# wifi.net
KiCad netlist of a schematic drawn in Altium Designer
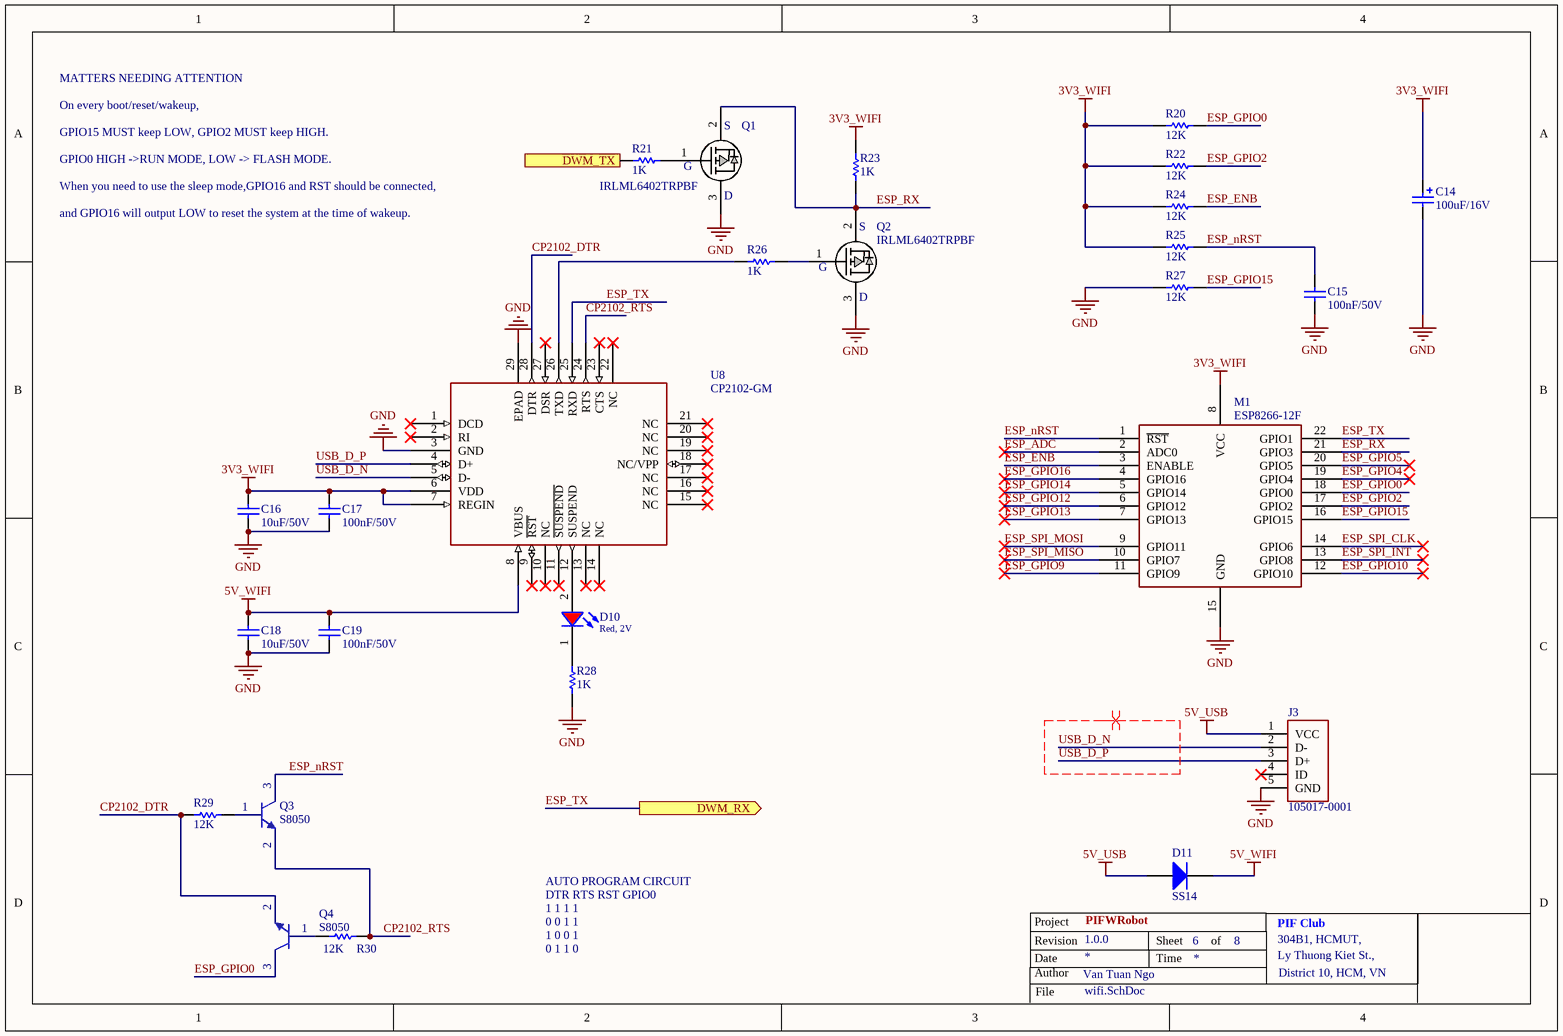
[diagram p0: wifi.SchDoc]

(export (version "E")
  (design (tool "Eeschema 10.0.6"))
  (components
    (comp (ref "C14")
      (value "100uF/16V")
      (footprint "CAP_SM_TAN")
      (fields
        (field (name "MANUFACTURER") "Nichicon")
        (field (name "MANUFACTURER PART NUMBER") "UWX1C101MCL1GB")
        (field (name "Comment") "TAJB107M006RNJ")
      )
      (libsource (lib "Capacitor") (part "Cap-Tan-100uF-16V"))
    )
    (comp (ref "C15")
      (value "100nF/50V")
      (footprint "CAP-SM-0805")
      (description "CAP CER 0.1UF 50V Y5V 0805")
      (fields
        (field (name "MANUFACTURER") "Samsung Electro-Mechanics")
        (field (name "MANUFACTURER PART NUMBER") "CL21F104ZBCNNNC")
      )
      (libsource (lib "Capacitor") (part "Cap-100nF-50V-0805"))
    )
    (comp (ref "C16")
      (value "10uF/50V")
      (footprint "CAP-SM-0805")
      (description "CAP CER 10UF 50V X5R 0805")
      (fields
        (field (name "MANUFACTURER") "Yageo")
        (field (name "MANUFACTURER PART NUMBER") "CC0805KKX5R9BB106")
      )
      (libsource (lib "capacitor-smd") (part "Cap-10uF-50V-0805"))
    )
    (comp (ref "C17")
      (value "100nF/50V")
      (footprint "CAP-SM-0805")
      (description "CAP CER 0.1UF 50V Y5V 0805")
      (fields
        (field (name "MANUFACTURER") "Samsung Electro-Mechanics")
        (field (name "MANUFACTURER PART NUMBER") "CL21F104ZBCNNNC")
      )
      (libsource (lib "capacitor-smd") (part "Cap-100nF-50V-0805"))
    )
    (comp (ref "C18")
      (value "10uF/50V")
      (footprint "CAP-SM-0805")
      (description "CAP CER 10UF 50V X5R 0805")
      (fields
        (field (name "MANUFACTURER") "Yageo")
        (field (name "MANUFACTURER PART NUMBER") "CC0805KKX5R9BB106")
      )
      (libsource (lib "capacitor-smd") (part "Cap-10uF-50V-0805"))
    )
    (comp (ref "C19")
      (value "100nF/50V")
      (footprint "CAP-SM-0805")
      (description "CAP CER 0.1UF 50V Y5V 0805")
      (fields
        (field (name "MANUFACTURER") "Samsung Electro-Mechanics")
        (field (name "MANUFACTURER PART NUMBER") "CL21F104ZBCNNNC")
      )
      (libsource (lib "capacitor-smd") (part "Cap-100nF-50V-0805"))
    )
    (comp (ref "D10")
      (value "Red, 2V")
      (footprint "WL-SMCW_0805")
      (description "WL-SMCW SMT Mono-color Chip LED Waterclear, size 0805, Red, 2V, 140deg")
      (fields
        (field (name "PART NUMBER") "150080RS75000")
        (field (name "LOCAL SUPPLIER PARTNUMBER") "x")
        (field (name "PUBLISHER") "Wurth Elektronik")
      )
      (libsource (lib "LED") (part "0805-Red"))
    )
    (comp (ref "D11")
      (value "SS14")
      (footprint "SS14")
      (description "DIODE SCHOTTKY 40V 1A SMA")
      (fields (field (name "MANUFACTURER") "ON Semiconductor"))
      (libsource (lib "Diode") (part "Diode-SS14"))
    )
    (comp (ref "J3")
      (value "105017-0001")
      (footprint "Micro-USB-Female")
      (description "CONN RCPT USB2.0 MICRO B SMD R/A")
      (fields
        (field (name "LOCAL SUPPLIER PART NUMBER") "x")
        (field (name "COPYRIGHT") "Copyright (C) 2018 Accelerated Designs. All rights reserved")
      )
      (libsource (lib "header-connector") (part "Micro-USB-Female"))
    )
    (comp (ref "M1")
      (value "ESP8266-12F")
      (footprint "ESP8266-12F")
      (fields (field (name "LOCAL SUPPLIER PART NUMBER") "x"))
      (libsource (lib "PIFWRobot") (part "ESP8266-12F"))
    )
    (comp (ref "Q1")
      (value "IRLML6402TRPBF")
      (footprint "SOT23_NEX")
      (description "P-Channel 20V 3.7A (Ta) 1.3W (Ta) Surface Mount Micro3™/SOT-23")
      (libsource (lib "MOSFET") (part "IRLML6402TRPBF"))
    )
    (comp (ref "Q2")
      (value "IRLML6402TRPBF")
      (footprint "SOT23_NEX")
      (description "P-Channel 20V 3.7A (Ta) 1.3W (Ta) Surface Mount Micro3™/SOT-23")
      (libsource (lib "MOSFET") (part "IRLML6402TRPBF"))
    )
    (comp (ref "Q3") (value "S8050") (footprint "SOT23_NEX") (libsource (lib "BJT") (part "S8050")))
    (comp (ref "Q4") (value "S8050") (footprint "SOT23_NEX") (libsource (lib "BJT") (part "S8050")))
    (comp (ref "R20")
      (value "12K")
      (footprint "resistor-smd:RES-SM-0805")
      (description "RES 12 KOHM JUMPER 0805")
      (fields
        (field (name "MANUFACTURER") "Vishay Thin Film")
        (field (name "MANUFACTURER PART NUMBER") "PAT0805E3121BST1")
      )
      (libsource (lib "resistor-smd") (part "Res-12K-0805"))
    )
    (comp (ref "R21")
      (value "1K")
      (footprint "resistor-smd:RES-SM-0805")
      (description "RES 1K OHM 1% 1/4W 0805")
      (fields
        (field (name "MANUFACTURER") "Stackpole Electronics Inc")
        (field (name "MANUFACTURER PART NUMBER") "RNCP0805FTD1K00")
      )
      (libsource (lib "resistor-smd") (part "Res-1K-0805"))
    )
    (comp (ref "R22")
      (value "12K")
      (footprint "resistor-smd:RES-SM-0805")
      (description "RES 12 KOHM JUMPER 0805")
      (fields
        (field (name "MANUFACTURER") "Vishay Thin Film")
        (field (name "MANUFACTURER PART NUMBER") "PAT0805E3121BST1")
      )
      (libsource (lib "resistor-smd") (part "Res-12K-0805"))
    )
    (comp (ref "R23")
      (value "1K")
      (footprint "resistor-smd:RES-SM-0805")
      (description "RES 1K OHM 1% 1/4W 0805")
      (fields
        (field (name "MANUFACTURER") "Stackpole Electronics Inc")
        (field (name "MANUFACTURER PART NUMBER") "RNCP0805FTD1K00")
      )
      (libsource (lib "resistor-smd") (part "Res-1K-0805"))
    )
    (comp (ref "R24")
      (value "12K")
      (footprint "resistor-smd:RES-SM-0805")
      (description "RES 12 KOHM JUMPER 0805")
      (fields
        (field (name "MANUFACTURER") "Vishay Thin Film")
        (field (name "MANUFACTURER PART NUMBER") "PAT0805E3121BST1")
      )
      (libsource (lib "resistor-smd") (part "Res-12K-0805"))
    )
    (comp (ref "R25")
      (value "12K")
      (footprint "resistor-smd:RES-SM-0805")
      (description "RES 12 KOHM JUMPER 0805")
      (fields
        (field (name "MANUFACTURER") "Vishay Thin Film")
        (field (name "MANUFACTURER PART NUMBER") "PAT0805E3121BST1")
      )
      (libsource (lib "resistor-smd") (part "Res-12K-0805"))
    )
    (comp (ref "R26")
      (value "1K")
      (footprint "resistor-smd:RES-SM-0805")
      (description "RES 1K OHM 1% 1/4W 0805")
      (fields
        (field (name "MANUFACTURER") "Stackpole Electronics Inc")
        (field (name "MANUFACTURER PART NUMBER") "RNCP0805FTD1K00")
      )
      (libsource (lib "resistor-smd") (part "Res-1K-0805"))
    )
    (comp (ref "R27")
      (value "12K")
      (footprint "resistor-smd:RES-SM-0805")
      (description "RES 12 KOHM JUMPER 0805")
      (fields
        (field (name "MANUFACTURER") "Vishay Thin Film")
        (field (name "MANUFACTURER PART NUMBER") "PAT0805E3121BST1")
      )
      (libsource (lib "resistor-smd") (part "Res-12K-0805"))
    )
    (comp (ref "R28")
      (value "1K")
      (footprint "resistor-smd:RES-SM-0805")
      (description "RES 1K OHM 1% 1/4W 0805")
      (fields
        (field (name "MANUFACTURER") "Stackpole Electronics Inc")
        (field (name "MANUFACTURER PART NUMBER") "RNCP0805FTD1K00")
      )
      (libsource (lib "resistor-smd") (part "Res-1K-0805"))
    )
    (comp (ref "R29")
      (value "12K")
      (footprint "resistor-smd:RES-SM-0805")
      (description "RES 12 KOHM JUMPER 0805")
      (fields
        (field (name "MANUFACTURER") "Vishay Thin Film")
        (field (name "MANUFACTURER PART NUMBER") "PAT0805E3121BST1")
      )
      (libsource (lib "resistor-smd") (part "Res-12K-0805"))
    )
    (comp (ref "R30")
      (value "12K")
      (footprint "resistor-smd:RES-SM-0805")
      (description "RES 12 KOHM JUMPER 0805")
      (fields
        (field (name "MANUFACTURER") "Vishay Thin Film")
        (field (name "MANUFACTURER PART NUMBER") "PAT0805E3121BST1")
      )
      (libsource (lib "resistor-smd") (part "Res-12K-0805"))
    )
    (comp (ref "U8")
      (value "CP2102-GM")
      (footprint "QFN28_5X5_SIL")
      (fields (field (name "COPYRIGHT") "Copyright (C) 2018 Accelerated Designs. All rights reserved"))
      (libsource (lib "PIFWRobot") (part "CP2102-GM"))
    )
  )
  (nets
    (net (code "1") (name "/CP2102_DTR") (class "Default")
      (node (ref "Q4") (pin "2") (pinfunction "E_2") (pintype "passive"))
      (node (ref "R29") (pin "1") (pinfunction "1_1") (pintype "passive"))
      (node (ref "U8") (pin "28") (pinfunction "DTR_28") (pintype "output"))
    )
    (net (code "2") (name "/CP2102_RTS") (class "Default")
      (node (ref "Q3") (pin "2") (pinfunction "E_2") (pintype "passive"))
      (node (ref "R30") (pin "2") (pinfunction "2_2") (pintype "passive"))
      (node (ref "U8") (pin "24") (pinfunction "RTS_24") (pintype "output"))
    )
    (net (code "3") (name "/DWM_TX") (class "Default")
      (node (ref "R21") (pin "1") (pinfunction "1_1") (pintype "passive"))
    )
    (net (code "4") (name "/ESP_ADC") (class "Default")
      (node (ref "M1") (pin "2") (pinfunction "ADC0_2") (pintype "passive+no_connect"))
    )
    (net (code "5") (name "/ESP_ENB") (class "Default")
      (node (ref "M1") (pin "3") (pinfunction "ENABLE_3") (pintype "passive"))
      (node (ref "R24") (pin "2") (pinfunction "2_2") (pintype "passive"))
    )
    (net (code "6") (name "/ESP_GPIO0") (class "Default")
      (node (ref "M1") (pin "18") (pinfunction "GPIO0_18") (pintype "passive"))
      (node (ref "Q4") (pin "3") (pinfunction "C_3") (pintype "passive"))
      (node (ref "R20") (pin "2") (pinfunction "2_2") (pintype "passive"))
    )
    (net (code "7") (name "/ESP_GPIO2") (class "Default")
      (node (ref "M1") (pin "17") (pinfunction "GPIO2_17") (pintype "passive"))
      (node (ref "R22") (pin "2") (pinfunction "2_2") (pintype "passive"))
    )
    (net (code "8") (name "/ESP_GPIO4") (class "Default")
      (node (ref "M1") (pin "19") (pinfunction "GPIO4_19") (pintype "passive+no_connect"))
    )
    (net (code "9") (name "/ESP_GPIO5") (class "Default")
      (node (ref "M1") (pin "20") (pinfunction "GPIO5_20") (pintype "passive+no_connect"))
    )
    (net (code "10") (name "/ESP_GPIO9") (class "Default")
      (node (ref "M1") (pin "11") (pinfunction "GPIO9_11") (pintype "passive+no_connect"))
    )
    (net (code "11") (name "/ESP_GPIO10") (class "Default")
      (node (ref "M1") (pin "12") (pinfunction "GPIO10_12") (pintype "passive+no_connect"))
    )
    (net (code "12") (name "/ESP_GPIO12") (class "Default")
      (node (ref "M1") (pin "6") (pinfunction "GPIO12_6") (pintype "passive+no_connect"))
    )
    (net (code "13") (name "/ESP_GPIO13") (class "Default")
      (node (ref "M1") (pin "7") (pinfunction "GPIO13_7") (pintype "passive+no_connect"))
    )
    (net (code "14") (name "/ESP_GPIO14") (class "Default")
      (node (ref "M1") (pin "5") (pinfunction "GPIO14_5") (pintype "passive+no_connect"))
    )
    (net (code "15") (name "/ESP_GPIO15") (class "Default")
      (node (ref "M1") (pin "16") (pinfunction "GPIO15_16") (pintype "passive"))
      (node (ref "R27") (pin "2") (pinfunction "2_2") (pintype "passive"))
    )
    (net (code "16") (name "/ESP_GPIO16") (class "Default")
      (node (ref "M1") (pin "4") (pinfunction "GPIO16_4") (pintype "passive+no_connect"))
    )
    (net (code "17") (name "/ESP_RX") (class "Default")
      (node (ref "M1") (pin "21") (pinfunction "GPIO3_21") (pintype "passive"))
      (node (ref "Q1") (pin "2") (pinfunction "S_2") (pintype "passive"))
      (node (ref "Q2") (pin "2") (pinfunction "S_2") (pintype "passive"))
      (node (ref "R23") (pin "1") (pinfunction "1_1") (pintype "passive"))
    )
    (net (code "18") (name "/ESP_SPI_CLK") (class "Default")
      (node (ref "M1") (pin "14") (pinfunction "GPIO6_14") (pintype "passive+no_connect"))
    )
    (net (code "19") (name "/ESP_SPI_INT") (class "Default")
      (node (ref "M1") (pin "13") (pinfunction "GPIO8_13") (pintype "passive+no_connect"))
    )
    (net (code "20") (name "/ESP_SPI_MISO") (class "Default")
      (node (ref "M1") (pin "10") (pinfunction "GPIO7_10") (pintype "passive+no_connect"))
    )
    (net (code "21") (name "/ESP_SPI_MOSI") (class "Default")
      (node (ref "M1") (pin "9") (pinfunction "GPIO11_9") (pintype "passive+no_connect"))
    )
    (net (code "22") (name "/ESP_TX") (class "Default")
      (node (ref "M1") (pin "22") (pinfunction "GPIO1_22") (pintype "passive"))
      (node (ref "U8") (pin "25") (pinfunction "RXD_25") (pintype "input"))
    )
    (net (code "23") (name "/ESP_nRST") (class "Default")
      (node (ref "C15") (pin "2") (pinfunction "2_2") (pintype "passive"))
      (node (ref "M1") (pin "1") (pinfunction "~{RST}_1") (pintype "passive"))
      (node (ref "Q3") (pin "3") (pinfunction "C_3") (pintype "passive"))
      (node (ref "R25") (pin "2") (pinfunction "2_2") (pintype "passive"))
    )
    (net (code "24") (name "/USB_D_N") (class "Default")
      (node (ref "J3") (pin "2") (pinfunction "D-_2") (pintype "passive"))
      (node (ref "U8") (pin "5") (pinfunction "D-_5") (pintype "bidirectional"))
    )
    (net (code "25") (name "/USB_D_P") (class "Default")
      (node (ref "J3") (pin "3") (pinfunction "D+_3") (pintype "passive"))
      (node (ref "U8") (pin "4") (pinfunction "D+_4") (pintype "bidirectional"))
    )
    (net (code "26") (name "3V3_WIFI") (class "Default")
      (node (ref "C14") (pin "1") (pinfunction "1_1") (pintype "passive"))
      (node (ref "C16") (pin "2") (pinfunction "2_2") (pintype "passive"))
      (node (ref "C17") (pin "2") (pinfunction "2_2") (pintype "passive"))
      (node (ref "M1") (pin "8") (pinfunction "VCC_8") (pintype "passive"))
      (node (ref "R20") (pin "1") (pinfunction "1_1") (pintype "passive"))
      (node (ref "R22") (pin "1") (pinfunction "1_1") (pintype "passive"))
      (node (ref "R23") (pin "2") (pinfunction "2_2") (pintype "passive"))
      (node (ref "R24") (pin "1") (pinfunction "1_1") (pintype "passive"))
      (node (ref "R25") (pin "1") (pinfunction "1_1") (pintype "passive"))
      (node (ref "U8") (pin "6") (pinfunction "VDD_6") (pintype "power_in"))
      (node (ref "U8") (pin "7") (pinfunction "REGIN_7") (pintype "input"))
    )
    (net (code "27") (name "5V_USB") (class "Default")
      (node (ref "D11") (pin "2") (pinfunction "A_2") (pintype "passive"))
      (node (ref "J3") (pin "1") (pinfunction "VCC_1") (pintype "power_in"))
    )
    (net (code "28") (name "5V_WIFI") (class "Default")
      (node (ref "C18") (pin "2") (pinfunction "2_2") (pintype "passive"))
      (node (ref "C19") (pin "2") (pinfunction "2_2") (pintype "passive"))
      (node (ref "D11") (pin "1") (pinfunction "K_1") (pintype "passive"))
      (node (ref "U8") (pin "8") (pinfunction "VBUS_8") (pintype "input"))
    )
    (net (code "29") (name "GND") (class "Default")
      (node (ref "C14") (pin "2") (pinfunction "2_2") (pintype "passive"))
      (node (ref "C15") (pin "1") (pinfunction "1_1") (pintype "passive"))
      (node (ref "C16") (pin "1") (pinfunction "1_1") (pintype "passive"))
      (node (ref "C17") (pin "1") (pinfunction "1_1") (pintype "passive"))
      (node (ref "C18") (pin "1") (pinfunction "1_1") (pintype "passive"))
      (node (ref "C19") (pin "1") (pinfunction "1_1") (pintype "passive"))
      (node (ref "J3") (pin "5") (pinfunction "GND_5") (pintype "passive"))
      (node (ref "M1") (pin "15") (pinfunction "GND_15") (pintype "passive"))
      (node (ref "Q1") (pin "3") (pinfunction "D_3") (pintype "passive"))
      (node (ref "Q2") (pin "3") (pinfunction "D_3") (pintype "passive"))
      (node (ref "R27") (pin "1") (pinfunction "1_1") (pintype "passive"))
      (node (ref "R28") (pin "1") (pinfunction "1_1") (pintype "passive"))
      (node (ref "U8") (pin "29") (pinfunction "EPAD_29") (pintype "passive"))
      (node (ref "U8") (pin "3") (pinfunction "GND_3") (pintype "power_in"))
    )
    (net (code "30") (name "Net-(D10-A)") (class "Default")
      (node (ref "D10") (pin "2") (pinfunction "A_2") (pintype "passive"))
      (node (ref "U8") (pin "12") (pinfunction "SUSPEND_12") (pintype "output"))
    )
    (net (code "31") (name "Net-(D10-K)") (class "Default")
      (node (ref "D10") (pin "1") (pinfunction "K_1") (pintype "passive"))
      (node (ref "R28") (pin "2") (pinfunction "2_2") (pintype "passive"))
    )
    (net (code "32") (name "Net-(Q1-G)") (class "Default")
      (node (ref "Q1") (pin "1") (pinfunction "G_1") (pintype "passive"))
      (node (ref "R21") (pin "2") (pinfunction "2_2") (pintype "passive"))
    )
    (net (code "33") (name "Net-(Q2-G)") (class "Default")
      (node (ref "Q2") (pin "1") (pinfunction "G_1") (pintype "passive"))
      (node (ref "R26") (pin "2") (pinfunction "2_2") (pintype "passive"))
    )
    (net (code "34") (name "Net-(Q3-B)") (class "Default")
      (node (ref "Q3") (pin "1") (pinfunction "B_1") (pintype "passive"))
      (node (ref "R29") (pin "2") (pinfunction "2_2") (pintype "passive"))
    )
    (net (code "35") (name "Net-(Q4-B)") (class "Default")
      (node (ref "Q4") (pin "1") (pinfunction "B_1") (pintype "passive"))
      (node (ref "R30") (pin "1") (pinfunction "1_1") (pintype "passive"))
    )
    (net (code "36") (name "Net-(U8-TXD)") (class "Default")
      (node (ref "R26") (pin "1") (pinfunction "1_1") (pintype "passive"))
      (node (ref "U8") (pin "26") (pinfunction "TXD_26") (pintype "output"))
    )
    (net (code "37") (name "unconnected-(J3-ID-Pad4)") (class "Default")
      (node (ref "J3") (pin "4") (pinfunction "ID_4") (pintype "passive+no_connect"))
    )
    (net (code "38") (name "unconnected-(U8-CTS-Pad23)") (class "Default")
      (node (ref "U8") (pin "23") (pinfunction "CTS_23") (pintype "input+no_connect"))
    )
    (net (code "39") (name "unconnected-(U8-DCD-Pad1)") (class "Default")
      (node (ref "U8") (pin "1") (pinfunction "DCD_1") (pintype "input+no_connect"))
    )
    (net (code "40") (name "unconnected-(U8-DSR-Pad27)") (class "Default")
      (node (ref "U8") (pin "27") (pinfunction "DSR_27") (pintype "input+no_connect"))
    )
    (net (code "41") (name "unconnected-(U8-NC-Pad10)") (class "Default")
      (node (ref "U8") (pin "10") (pinfunction "NC_10") (pintype "passive+no_connect"))
    )
    (net (code "42") (name "unconnected-(U8-NC-Pad13)") (class "Default")
      (node (ref "U8") (pin "13") (pinfunction "NC_13") (pintype "passive+no_connect"))
    )
    (net (code "43") (name "unconnected-(U8-NC-Pad14)") (class "Default")
      (node (ref "U8") (pin "14") (pinfunction "NC_14") (pintype "passive+no_connect"))
    )
    (net (code "44") (name "unconnected-(U8-NC-Pad15)") (class "Default")
      (node (ref "U8") (pin "15") (pinfunction "NC_15") (pintype "passive+no_connect"))
    )
    (net (code "45") (name "unconnected-(U8-NC-Pad16)") (class "Default")
      (node (ref "U8") (pin "16") (pinfunction "NC_16") (pintype "passive+no_connect"))
    )
    (net (code "46") (name "unconnected-(U8-NC-Pad17)") (class "Default")
      (node (ref "U8") (pin "17") (pinfunction "NC_17") (pintype "passive+no_connect"))
    )
    (net (code "47") (name "unconnected-(U8-NC-Pad19)") (class "Default")
      (node (ref "U8") (pin "19") (pinfunction "NC_19") (pintype "passive+no_connect"))
    )
    (net (code "48") (name "unconnected-(U8-NC-Pad20)") (class "Default")
      (node (ref "U8") (pin "20") (pinfunction "NC_20") (pintype "passive+no_connect"))
    )
    (net (code "49") (name "unconnected-(U8-NC-Pad21)") (class "Default")
      (node (ref "U8") (pin "21") (pinfunction "NC_21") (pintype "passive+no_connect"))
    )
    (net (code "50") (name "unconnected-(U8-NC-Pad22)") (class "Default")
      (node (ref "U8") (pin "22") (pinfunction "NC_22") (pintype "passive+no_connect"))
    )
    (net (code "51") (name "unconnected-(U8-NC{slash}VPP-Pad18)") (class "Default")
      (node (ref "U8") (pin "18") (pinfunction "NC/VPP_18") (pintype "bidirectional+no_connect"))
    )
    (net (code "52") (name "unconnected-(U8-RI-Pad2)") (class "Default")
      (node (ref "U8") (pin "2") (pinfunction "RI_2") (pintype "input+no_connect"))
    )
    (net (code "53") (name "unconnected-(U8-~{RST}-Pad9)") (class "Default")
      (node (ref "U8") (pin "9") (pinfunction "~{RST}_9") (pintype "bidirectional+no_connect"))
    )
    (net (code "54") (name "unconnected-(U8-~{SUSPEND}-Pad11)") (class "Default")
      (node (ref "U8") (pin "11") (pinfunction "~{SUSPEND}_11") (pintype "output+no_connect"))
    )
  )
)
